# parallel_jtag_programmer_smd.net
KiCad netlist of a schematic drawn in EAGLE
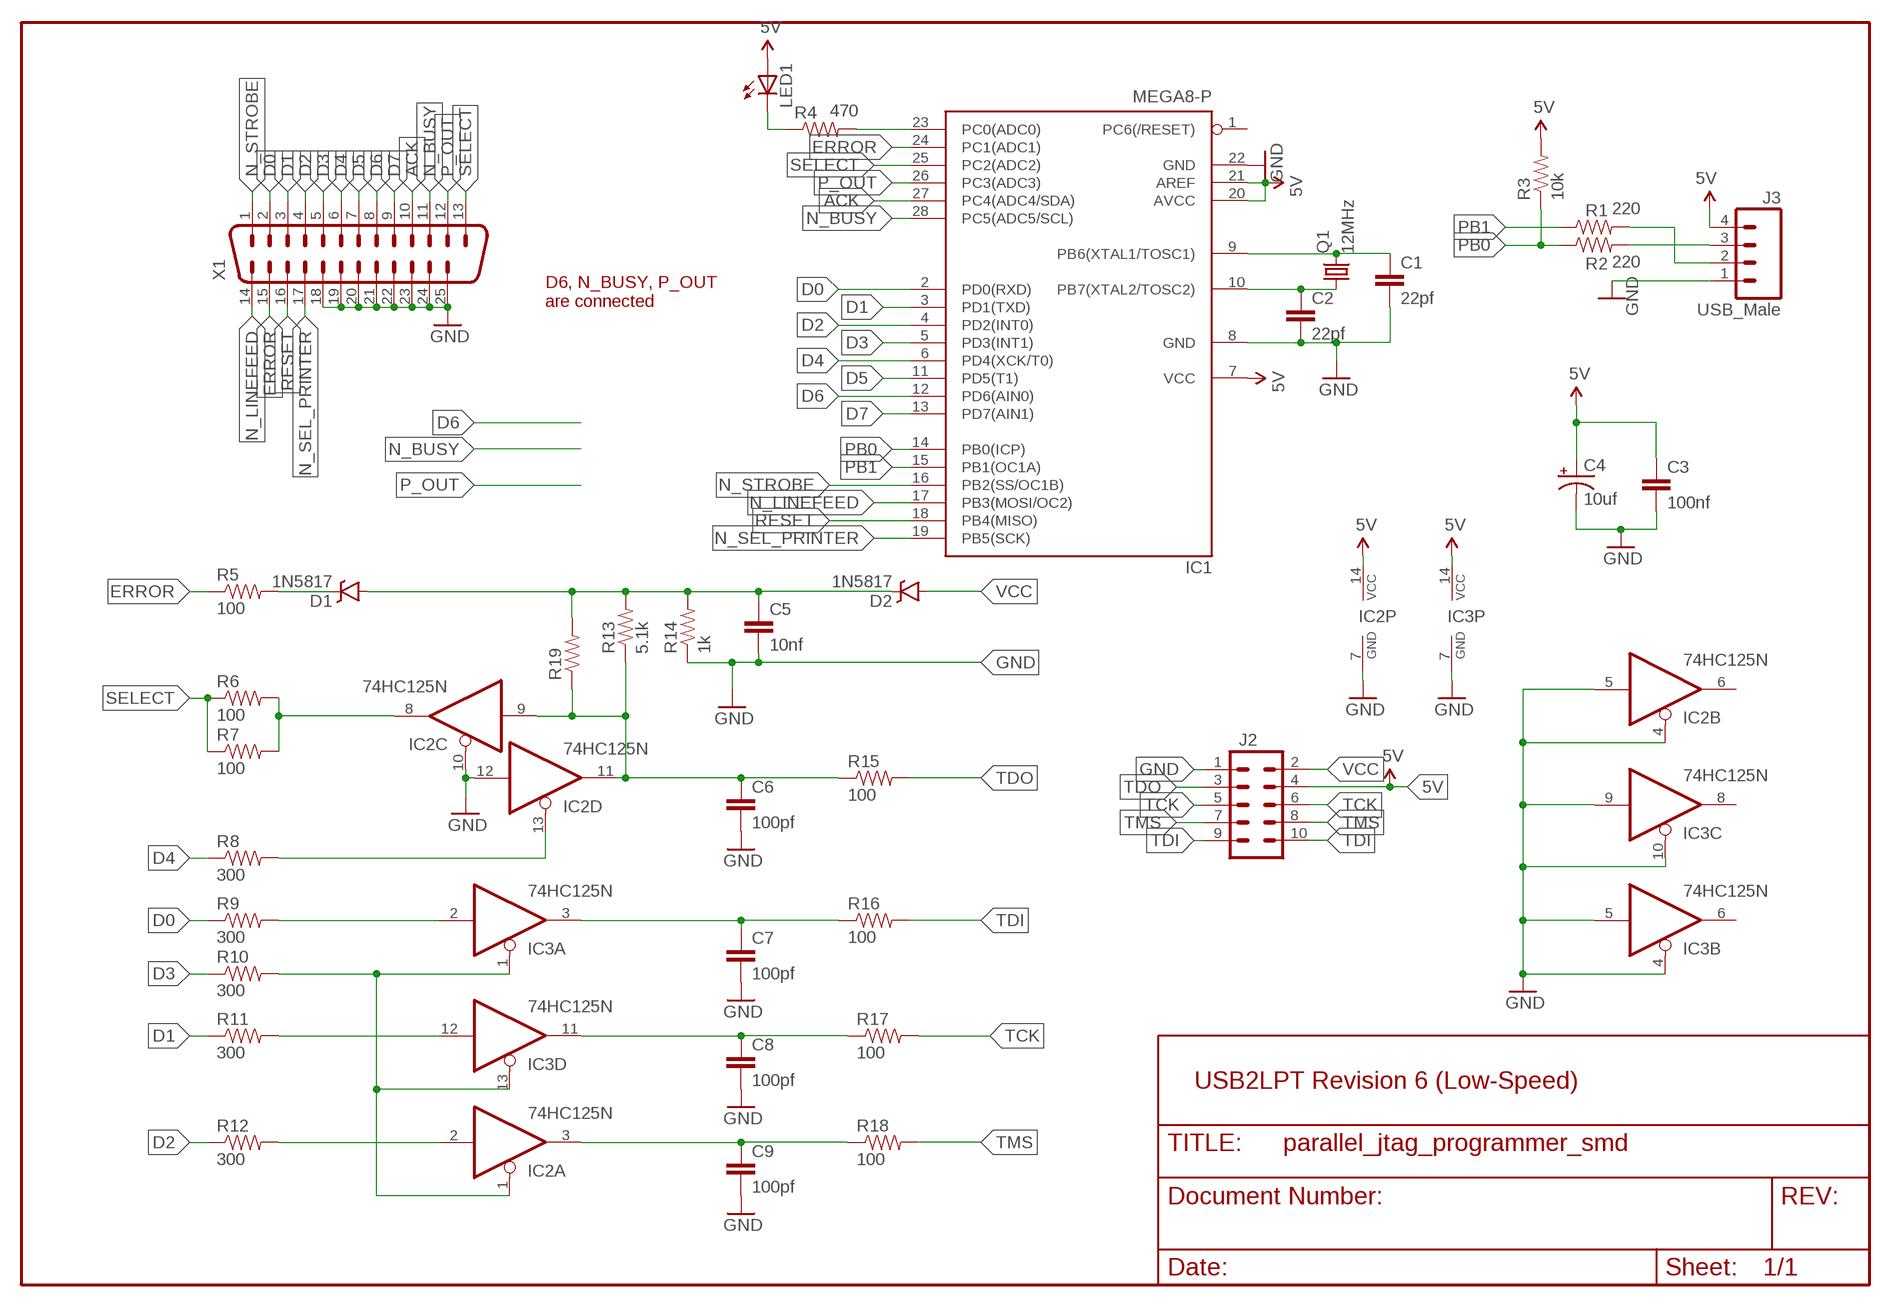
[diagram p0: schematic, sheet 1]

(export (version "E")
  (design (tool "Eeschema 10.0.6"))
  (components
    (comp (ref "C1")
      (value "22pf")
      (footprint "eagle-import:CAP-PTH-SMALL")
      (libsource (lib "eagle-import") (part "CAPPTH"))
    )
    (comp (ref "C2")
      (value "22pf")
      (footprint "eagle-import:CAP-PTH-SMALL")
      (libsource (lib "eagle-import") (part "CAPPTH"))
    )
    (comp (ref "C3")
      (value "100nf")
      (footprint "eagle-import:1206")
      (libsource (lib "eagle-import") (part "CAP1206"))
    )
    (comp (ref "C4")
      (value "10uf")
      (footprint "eagle-import:EIA3216")
      (libsource (lib "eagle-import") (part "CAP_POL1206"))
    )
    (comp (ref "C5")
      (value "10nf")
      (footprint "eagle-import:1206")
      (libsource (lib "eagle-import") (part "CAP1206"))
    )
    (comp (ref "C6")
      (value "100pf")
      (footprint "eagle-import:1206")
      (libsource (lib "eagle-import") (part "CAP1206"))
    )
    (comp (ref "C7")
      (value "100pf")
      (footprint "eagle-import:1206")
      (libsource (lib "eagle-import") (part "CAP1206"))
    )
    (comp (ref "C8")
      (value "100pf")
      (footprint "eagle-import:1206")
      (libsource (lib "eagle-import") (part "CAP1206"))
    )
    (comp (ref "C9")
      (value "100pf")
      (footprint "eagle-import:1206")
      (libsource (lib "eagle-import") (part "CAP1206"))
    )
    (comp (ref "D1")
      (value "1N5817")
      (footprint "eagle-import:SMA-DIODE")
      (libsource (lib "eagle-import") (part "DIODE-SCHOTTKY-B340A"))
    )
    (comp (ref "D2")
      (value "1N5817")
      (footprint "eagle-import:SMA-DIODE")
      (libsource (lib "eagle-import") (part "DIODE-SCHOTTKY-B340A"))
    )
    (comp (ref "IC1")
      (value "MEGA8-P")
      (footprint "eagle-import:DIL28-3")
      (libsource (lib "eagle-import") (part "MEGA8-P"))
    )
    (comp (ref "IC2")
      (value "74HC125N")
      (footprint "eagle-import:DIL14")
      (libsource (lib "eagle-import") (part "74125NHC"))
    )
    (comp (ref "IC3")
      (value "74HC125N")
      (footprint "eagle-import:DIL14")
      (libsource (lib "eagle-import") (part "74125NHC"))
    )
    (comp (ref "J2")
      (value "M05X2SHD")
      (footprint "eagle-import:2X5-SHROUDED")
      (libsource (lib "eagle-import") (part "M05X2SHD"))
    )
    (comp (ref "J3")
      (value "USB_Male")
      (footprint "eagle-import:1X04")
      (libsource (lib "eagle-import") (part "M04PTH"))
    )
    (comp (ref "LED1")
      (value "LED3MM")
      (footprint "eagle-import:LED3MM")
      (libsource (lib "eagle-import") (part "LED3MM"))
    )
    (comp (ref "Q1")
      (value "12MHz")
      (footprint "eagle-import:HC49U-V")
      (libsource (lib "eagle-import") (part "CRYSTALHC49U-V"))
    )
    (comp (ref "R1")
      (value "220")
      (footprint "eagle-import:1206")
      (libsource (lib "eagle-import") (part "RESISTOR1206"))
    )
    (comp (ref "R2")
      (value "220")
      (footprint "eagle-import:1206")
      (libsource (lib "eagle-import") (part "RESISTOR1206"))
    )
    (comp (ref "R3")
      (value "10k")
      (footprint "eagle-import:1206")
      (libsource (lib "eagle-import") (part "RESISTOR1206"))
    )
    (comp (ref "R4")
      (value "470")
      (footprint "eagle-import:1206")
      (libsource (lib "eagle-import") (part "RESISTOR1206"))
    )
    (comp (ref "R5")
      (value "100")
      (footprint "eagle-import:1206")
      (libsource (lib "eagle-import") (part "RESISTOR1206"))
    )
    (comp (ref "R6")
      (value "100")
      (footprint "eagle-import:1206")
      (libsource (lib "eagle-import") (part "RESISTOR1206"))
    )
    (comp (ref "R7")
      (value "100")
      (footprint "eagle-import:1206")
      (libsource (lib "eagle-import") (part "RESISTOR1206"))
    )
    (comp (ref "R8")
      (value "300")
      (footprint "eagle-import:1206")
      (libsource (lib "eagle-import") (part "RESISTOR1206"))
    )
    (comp (ref "R9")
      (value "300")
      (footprint "eagle-import:1206")
      (libsource (lib "eagle-import") (part "RESISTOR1206"))
    )
    (comp (ref "R10")
      (value "300")
      (footprint "eagle-import:1206")
      (libsource (lib "eagle-import") (part "RESISTOR1206"))
    )
    (comp (ref "R11")
      (value "300")
      (footprint "eagle-import:1206")
      (libsource (lib "eagle-import") (part "RESISTOR1206"))
    )
    (comp (ref "R12")
      (value "300")
      (footprint "eagle-import:1206")
      (libsource (lib "eagle-import") (part "RESISTOR1206"))
    )
    (comp (ref "R13")
      (value "5.1k")
      (footprint "eagle-import:1206")
      (libsource (lib "eagle-import") (part "RESISTOR1206"))
    )
    (comp (ref "R14")
      (value "1k")
      (footprint "eagle-import:1206")
      (libsource (lib "eagle-import") (part "RESISTOR1206"))
    )
    (comp (ref "R15")
      (value "100")
      (footprint "eagle-import:1206")
      (libsource (lib "eagle-import") (part "RESISTOR1206"))
    )
    (comp (ref "R16")
      (value "100")
      (footprint "eagle-import:1206")
      (libsource (lib "eagle-import") (part "RESISTOR1206"))
    )
    (comp (ref "R17")
      (value "100")
      (footprint "eagle-import:1206")
      (libsource (lib "eagle-import") (part "RESISTOR1206"))
    )
    (comp (ref "R18")
      (value "100")
      (footprint "eagle-import:1206")
      (libsource (lib "eagle-import") (part "RESISTOR1206"))
    )
    (comp (ref "R19")
      (value "RESISTOR1206")
      (footprint "eagle-import:1206")
      (libsource (lib "eagle-import") (part "RESISTOR1206"))
    )
    (comp (ref "X1")
      (value "DB25D")
      (footprint "eagle-import:M25D")
      (libsource (lib "eagle-import") (part "DB25D"))
    )
  )
  (nets
    (net (code "1") (name "5V") (class "Default")
      (node (ref "C3") (pin "1") (pinfunction "1_1") (pintype "passive"))
      (node (ref "C4") (pin "A") (pinfunction "+_A") (pintype "passive"))
      (node (ref "IC1") (pin "20") (pinfunction "AVCC_20") (pintype "power_in"))
      (node (ref "IC1") (pin "21") (pinfunction "AREF_21") (pintype "passive"))
      (node (ref "IC1") (pin "7") (pinfunction "VCC_7") (pintype "power_in"))
      (node (ref "IC2") (pin "14") (pinfunction "VCC_14") (pintype "power_in"))
      (node (ref "IC3") (pin "14") (pinfunction "VCC_14") (pintype "power_in"))
      (node (ref "J2") (pin "4") (pinfunction "4_4") (pintype "passive"))
      (node (ref "J3") (pin "4") (pinfunction "4_4") (pintype "passive"))
      (node (ref "LED1") (pin "A") (pinfunction "A_A") (pintype "passive"))
      (node (ref "R3") (pin "2") (pinfunction "2_2") (pintype "passive"))
    )
    (net (code "2") (name "ACK") (class "Default")
      (node (ref "IC1") (pin "27") (pinfunction "PC4(ADC4/SDA)_27") (pintype "bidirectional"))
      (node (ref "X1") (pin "10") (pinfunction "10_10") (pintype "passive"))
    )
    (net (code "3") (name "D0") (class "Default")
      (node (ref "IC1") (pin "2") (pinfunction "PD0(RXD)_2") (pintype "bidirectional"))
      (node (ref "R9") (pin "1") (pinfunction "1_1") (pintype "passive"))
      (node (ref "X1") (pin "2") (pinfunction "2_2") (pintype "passive"))
    )
    (net (code "4") (name "D1") (class "Default")
      (node (ref "IC1") (pin "3") (pinfunction "PD1(TXD)_3") (pintype "bidirectional"))
      (node (ref "R11") (pin "1") (pinfunction "1_1") (pintype "passive"))
      (node (ref "X1") (pin "3") (pinfunction "3_3") (pintype "passive"))
    )
    (net (code "5") (name "D2") (class "Default")
      (node (ref "IC1") (pin "4") (pinfunction "PD2(INT0)_4") (pintype "bidirectional"))
      (node (ref "R12") (pin "1") (pinfunction "1_1") (pintype "passive"))
      (node (ref "X1") (pin "4") (pinfunction "4_4") (pintype "passive"))
    )
    (net (code "6") (name "D3") (class "Default")
      (node (ref "IC1") (pin "5") (pinfunction "PD3(INT1)_5") (pintype "bidirectional"))
      (node (ref "R10") (pin "1") (pinfunction "1_1") (pintype "passive"))
      (node (ref "X1") (pin "5") (pinfunction "5_5") (pintype "passive"))
    )
    (net (code "7") (name "D4") (class "Default")
      (node (ref "IC1") (pin "6") (pinfunction "PD4(XCK/T0)_6") (pintype "bidirectional"))
      (node (ref "R8") (pin "1") (pinfunction "1_1") (pintype "passive"))
      (node (ref "X1") (pin "6") (pinfunction "6_6") (pintype "passive"))
    )
    (net (code "8") (name "D5") (class "Default")
      (node (ref "IC1") (pin "11") (pinfunction "PD5(T1)_11") (pintype "bidirectional"))
      (node (ref "X1") (pin "7") (pinfunction "7_7") (pintype "passive"))
    )
    (net (code "9") (name "D6") (class "Default")
      (node (ref "IC1") (pin "12") (pinfunction "PD6(AIN0)_12") (pintype "bidirectional"))
      (node (ref "X1") (pin "8") (pinfunction "8_8") (pintype "passive"))
    )
    (net (code "10") (name "D7") (class "Default")
      (node (ref "IC1") (pin "13") (pinfunction "PD7(AIN1)_13") (pintype "bidirectional"))
      (node (ref "X1") (pin "9") (pinfunction "9_9") (pintype "passive"))
    )
    (net (code "11") (name "ERROR") (class "Default")
      (node (ref "IC1") (pin "24") (pinfunction "PC1(ADC1)_24") (pintype "bidirectional"))
      (node (ref "R5") (pin "1") (pinfunction "1_1") (pintype "passive"))
      (node (ref "X1") (pin "15") (pinfunction "15_15") (pintype "passive"))
    )
    (net (code "12") (name "GND") (class "Default")
      (node (ref "C1") (pin "2") (pinfunction "2_2") (pintype "passive"))
      (node (ref "C2") (pin "2") (pinfunction "2_2") (pintype "passive"))
      (node (ref "C3") (pin "2") (pinfunction "2_2") (pintype "passive"))
      (node (ref "C4") (pin "C") (pinfunction "-_C") (pintype "passive"))
      (node (ref "C5") (pin "2") (pinfunction "2_2") (pintype "passive"))
      (node (ref "C6") (pin "2") (pinfunction "2_2") (pintype "passive"))
      (node (ref "C7") (pin "2") (pinfunction "2_2") (pintype "passive"))
      (node (ref "C8") (pin "2") (pinfunction "2_2") (pintype "passive"))
      (node (ref "C9") (pin "2") (pinfunction "2_2") (pintype "passive"))
      (node (ref "IC1") (pin "22") (pinfunction "GND_22") (pintype "power_in"))
      (node (ref "IC1") (pin "8") (pinfunction "GND_8") (pintype "power_in"))
      (node (ref "IC2") (pin "10") (pinfunction "OE_10") (pintype "input"))
      (node (ref "IC2") (pin "12") (pinfunction "I_12") (pintype "input"))
      (node (ref "IC2") (pin "4") (pinfunction "OE_4") (pintype "input"))
      (node (ref "IC2") (pin "5") (pinfunction "I_5") (pintype "input"))
      (node (ref "IC2") (pin "7") (pinfunction "GND_7") (pintype "power_in"))
      (node (ref "IC3") (pin "10") (pinfunction "OE_10") (pintype "input"))
      (node (ref "IC3") (pin "4") (pinfunction "OE_4") (pintype "input"))
      (node (ref "IC3") (pin "5") (pinfunction "I_5") (pintype "input"))
      (node (ref "IC3") (pin "7") (pinfunction "GND_7") (pintype "power_in"))
      (node (ref "IC3") (pin "9") (pinfunction "I_9") (pintype "input"))
      (node (ref "J2") (pin "1") (pinfunction "1_1") (pintype "passive"))
      (node (ref "J3") (pin "1") (pinfunction "1_1") (pintype "passive"))
      (node (ref "R14") (pin "1") (pinfunction "1_1") (pintype "passive"))
      (node (ref "X1") (pin "18") (pinfunction "18_18") (pintype "passive"))
      (node (ref "X1") (pin "19") (pinfunction "19_19") (pintype "passive"))
      (node (ref "X1") (pin "20") (pinfunction "20_20") (pintype "passive"))
      (node (ref "X1") (pin "21") (pinfunction "21_21") (pintype "passive"))
      (node (ref "X1") (pin "22") (pinfunction "22_22") (pintype "passive"))
      (node (ref "X1") (pin "23") (pinfunction "23_23") (pintype "passive"))
      (node (ref "X1") (pin "24") (pinfunction "24_24") (pintype "passive"))
      (node (ref "X1") (pin "25") (pinfunction "25_25") (pintype "passive"))
    )
    (net (code "13") (name "N_BUSY") (class "Default")
      (node (ref "IC1") (pin "28") (pinfunction "PC5(ADC5/SCL)_28") (pintype "bidirectional"))
      (node (ref "X1") (pin "11") (pinfunction "11_11") (pintype "passive"))
    )
    (net (code "14") (name "N_LINEFEED") (class "Default")
      (node (ref "IC1") (pin "17") (pinfunction "PB3(MOSI/OC2)_17") (pintype "bidirectional"))
      (node (ref "X1") (pin "14") (pinfunction "14_14") (pintype "passive"))
    )
    (net (code "15") (name "N_SEL_PRINTER") (class "Default")
      (node (ref "IC1") (pin "19") (pinfunction "PB5(SCK)_19") (pintype "bidirectional"))
      (node (ref "X1") (pin "17") (pinfunction "17_17") (pintype "passive"))
    )
    (net (code "16") (name "N_STROBE") (class "Default")
      (node (ref "IC1") (pin "16") (pinfunction "PB2(SS/OC1B)_16") (pintype "bidirectional"))
      (node (ref "X1") (pin "1") (pinfunction "1_1") (pintype "passive"))
    )
    (net (code "17") (name "Net-(C5-Pad1)") (class "Default")
      (node (ref "C5") (pin "1") (pinfunction "1_1") (pintype "passive"))
      (node (ref "D1") (pin "A") (pinfunction "A_A") (pintype "passive"))
      (node (ref "D2") (pin "C") (pinfunction "C_C") (pintype "passive"))
      (node (ref "R13") (pin "2") (pinfunction "2_2") (pintype "passive"))
      (node (ref "R14") (pin "2") (pinfunction "2_2") (pintype "passive"))
      (node (ref "R19") (pin "2") (pinfunction "2_2") (pintype "passive"))
    )
    (net (code "18") (name "Net-(D1-PadC)") (class "Default")
      (node (ref "D1") (pin "C") (pinfunction "C_C") (pintype "passive"))
      (node (ref "R5") (pin "2") (pinfunction "2_2") (pintype "passive"))
    )
    (net (code "19") (name "Net-(IC1-PB6(XTAL1{slash}TOSC1))") (class "Default")
      (node (ref "C1") (pin "1") (pinfunction "1_1") (pintype "passive"))
      (node (ref "IC1") (pin "9") (pinfunction "PB6(XTAL1/TOSC1)_9") (pintype "bidirectional"))
      (node (ref "Q1") (pin "2") (pinfunction "2_2") (pintype "passive"))
    )
    (net (code "20") (name "Net-(IC1-PB7(XTAL2{slash}TOSC2))") (class "Default")
      (node (ref "C2") (pin "1") (pinfunction "1_1") (pintype "passive"))
      (node (ref "IC1") (pin "10") (pinfunction "PB7(XTAL2/TOSC2)_10") (pintype "bidirectional"))
      (node (ref "Q1") (pin "1") (pinfunction "1_1") (pintype "passive"))
    )
    (net (code "21") (name "Net-(IC1-PC0(ADC0))") (class "Default")
      (node (ref "IC1") (pin "23") (pinfunction "PC0(ADC0)_23") (pintype "bidirectional"))
      (node (ref "R4") (pin "2") (pinfunction "2_2") (pintype "passive"))
    )
    (net (code "22") (name "Net-(IC2A-I)") (class "Default")
      (node (ref "IC2") (pin "2") (pinfunction "I_2") (pintype "input"))
      (node (ref "R12") (pin "2") (pinfunction "2_2") (pintype "passive"))
    )
    (net (code "23") (name "Net-(IC2A-O)") (class "Default")
      (node (ref "C9") (pin "1") (pinfunction "1_1") (pintype "passive"))
      (node (ref "IC2") (pin "3") (pinfunction "O_3") (pintype "tri_state"))
      (node (ref "R18") (pin "1") (pinfunction "1_1") (pintype "passive"))
    )
    (net (code "24") (name "Net-(IC2A-OE)") (class "Default")
      (node (ref "IC2") (pin "1") (pinfunction "OE_1") (pintype "input"))
      (node (ref "IC3") (pin "1") (pinfunction "OE_1") (pintype "input"))
      (node (ref "IC3") (pin "13") (pinfunction "OE_13") (pintype "input"))
      (node (ref "R10") (pin "2") (pinfunction "2_2") (pintype "passive"))
    )
    (net (code "25") (name "Net-(IC2C-I)") (class "Default")
      (node (ref "C6") (pin "1") (pinfunction "1_1") (pintype "passive"))
      (node (ref "IC2") (pin "11") (pinfunction "O_11") (pintype "tri_state"))
      (node (ref "IC2") (pin "9") (pinfunction "I_9") (pintype "input"))
      (node (ref "R13") (pin "1") (pinfunction "1_1") (pintype "passive"))
      (node (ref "R15") (pin "1") (pinfunction "1_1") (pintype "passive"))
      (node (ref "R19") (pin "1") (pinfunction "1_1") (pintype "passive"))
    )
    (net (code "26") (name "Net-(IC2C-O)") (class "Default")
      (node (ref "IC2") (pin "8") (pinfunction "O_8") (pintype "tri_state"))
      (node (ref "R6") (pin "2") (pinfunction "2_2") (pintype "passive"))
      (node (ref "R7") (pin "2") (pinfunction "2_2") (pintype "passive"))
    )
    (net (code "27") (name "Net-(IC2D-OE)") (class "Default")
      (node (ref "IC2") (pin "13") (pinfunction "OE_13") (pintype "input"))
      (node (ref "R8") (pin "2") (pinfunction "2_2") (pintype "passive"))
    )
    (net (code "28") (name "Net-(IC3A-I)") (class "Default")
      (node (ref "IC3") (pin "2") (pinfunction "I_2") (pintype "input"))
      (node (ref "R9") (pin "2") (pinfunction "2_2") (pintype "passive"))
    )
    (net (code "29") (name "Net-(IC3A-O)") (class "Default")
      (node (ref "C7") (pin "1") (pinfunction "1_1") (pintype "passive"))
      (node (ref "IC3") (pin "3") (pinfunction "O_3") (pintype "tri_state"))
      (node (ref "R16") (pin "1") (pinfunction "1_1") (pintype "passive"))
    )
    (net (code "30") (name "Net-(IC3D-I)") (class "Default")
      (node (ref "IC3") (pin "12") (pinfunction "I_12") (pintype "input"))
      (node (ref "R11") (pin "2") (pinfunction "2_2") (pintype "passive"))
    )
    (net (code "31") (name "Net-(IC3D-O)") (class "Default")
      (node (ref "C8") (pin "1") (pinfunction "1_1") (pintype "passive"))
      (node (ref "IC3") (pin "11") (pinfunction "O_11") (pintype "tri_state"))
      (node (ref "R17") (pin "1") (pinfunction "1_1") (pintype "passive"))
    )
    (net (code "32") (name "Net-(J3-Pad2)") (class "Default")
      (node (ref "J3") (pin "2") (pinfunction "2_2") (pintype "passive"))
      (node (ref "R1") (pin "2") (pinfunction "2_2") (pintype "passive"))
    )
    (net (code "33") (name "Net-(J3-Pad3)") (class "Default")
      (node (ref "J3") (pin "3") (pinfunction "3_3") (pintype "passive"))
      (node (ref "R2") (pin "2") (pinfunction "2_2") (pintype "passive"))
    )
    (net (code "34") (name "Net-(LED1-C)") (class "Default")
      (node (ref "LED1") (pin "K") (pinfunction "C_K") (pintype "passive"))
      (node (ref "R4") (pin "1") (pinfunction "1_1") (pintype "passive"))
    )
    (net (code "35") (name "PB0") (class "Default")
      (node (ref "IC1") (pin "14") (pinfunction "PB0(ICP)_14") (pintype "bidirectional"))
      (node (ref "R2") (pin "1") (pinfunction "1_1") (pintype "passive"))
      (node (ref "R3") (pin "1") (pinfunction "1_1") (pintype "passive"))
    )
    (net (code "36") (name "PB1") (class "Default")
      (node (ref "IC1") (pin "15") (pinfunction "PB1(OC1A)_15") (pintype "bidirectional"))
      (node (ref "R1") (pin "1") (pinfunction "1_1") (pintype "passive"))
    )
    (net (code "37") (name "P_OUT") (class "Default")
      (node (ref "IC1") (pin "26") (pinfunction "PC3(ADC3)_26") (pintype "bidirectional"))
      (node (ref "X1") (pin "12") (pinfunction "12_12") (pintype "passive"))
    )
    (net (code "38") (name "RESET") (class "Default")
      (node (ref "IC1") (pin "18") (pinfunction "PB4(MISO)_18") (pintype "bidirectional"))
      (node (ref "X1") (pin "16") (pinfunction "16_16") (pintype "passive"))
    )
    (net (code "39") (name "SELECT") (class "Default")
      (node (ref "IC1") (pin "25") (pinfunction "PC2(ADC2)_25") (pintype "bidirectional"))
      (node (ref "R6") (pin "1") (pinfunction "1_1") (pintype "passive"))
      (node (ref "R7") (pin "1") (pinfunction "1_1") (pintype "passive"))
      (node (ref "X1") (pin "13") (pinfunction "13_13") (pintype "passive"))
    )
    (net (code "40") (name "TCK") (class "Default")
      (node (ref "J2") (pin "5") (pinfunction "5_5") (pintype "passive"))
      (node (ref "J2") (pin "6") (pinfunction "6_6") (pintype "passive"))
      (node (ref "R17") (pin "2") (pinfunction "2_2") (pintype "passive"))
    )
    (net (code "41") (name "TDI") (class "Default")
      (node (ref "J2") (pin "10") (pinfunction "10_10") (pintype "passive"))
      (node (ref "J2") (pin "9") (pinfunction "9_9") (pintype "passive"))
      (node (ref "R16") (pin "2") (pinfunction "2_2") (pintype "passive"))
    )
    (net (code "42") (name "TDO") (class "Default")
      (node (ref "J2") (pin "3") (pinfunction "3_3") (pintype "passive"))
      (node (ref "R15") (pin "2") (pinfunction "2_2") (pintype "passive"))
    )
    (net (code "43") (name "TMS") (class "Default")
      (node (ref "J2") (pin "7") (pinfunction "7_7") (pintype "passive"))
      (node (ref "J2") (pin "8") (pinfunction "8_8") (pintype "passive"))
      (node (ref "R18") (pin "2") (pinfunction "2_2") (pintype "passive"))
    )
    (net (code "44") (name "VCC") (class "Default")
      (node (ref "D2") (pin "A") (pinfunction "A_A") (pintype "passive"))
      (node (ref "J2") (pin "2") (pinfunction "2_2") (pintype "passive"))
    )
    (net (code "45") (name "unconnected-(IC1-PC6({slash}RESET)-Pad1)") (class "Default")
      (node (ref "IC1") (pin "1") (pinfunction "PC6(/RESET)_1") (pintype "bidirectional"))
    )
    (net (code "46") (name "unconnected-(IC2B-O-Pad6)") (class "Default")
      (node (ref "IC2") (pin "6") (pinfunction "O_6") (pintype "tri_state"))
    )
    (net (code "47") (name "unconnected-(IC3B-O-Pad6)") (class "Default")
      (node (ref "IC3") (pin "6") (pinfunction "O_6") (pintype "tri_state"))
    )
    (net (code "48") (name "unconnected-(IC3C-O-Pad8)") (class "Default")
      (node (ref "IC3") (pin "8") (pinfunction "O_8") (pintype "tri_state"))
    )
  )
)
